# comms_2.net
KiCad netlist of a schematic drawn in EAGLE
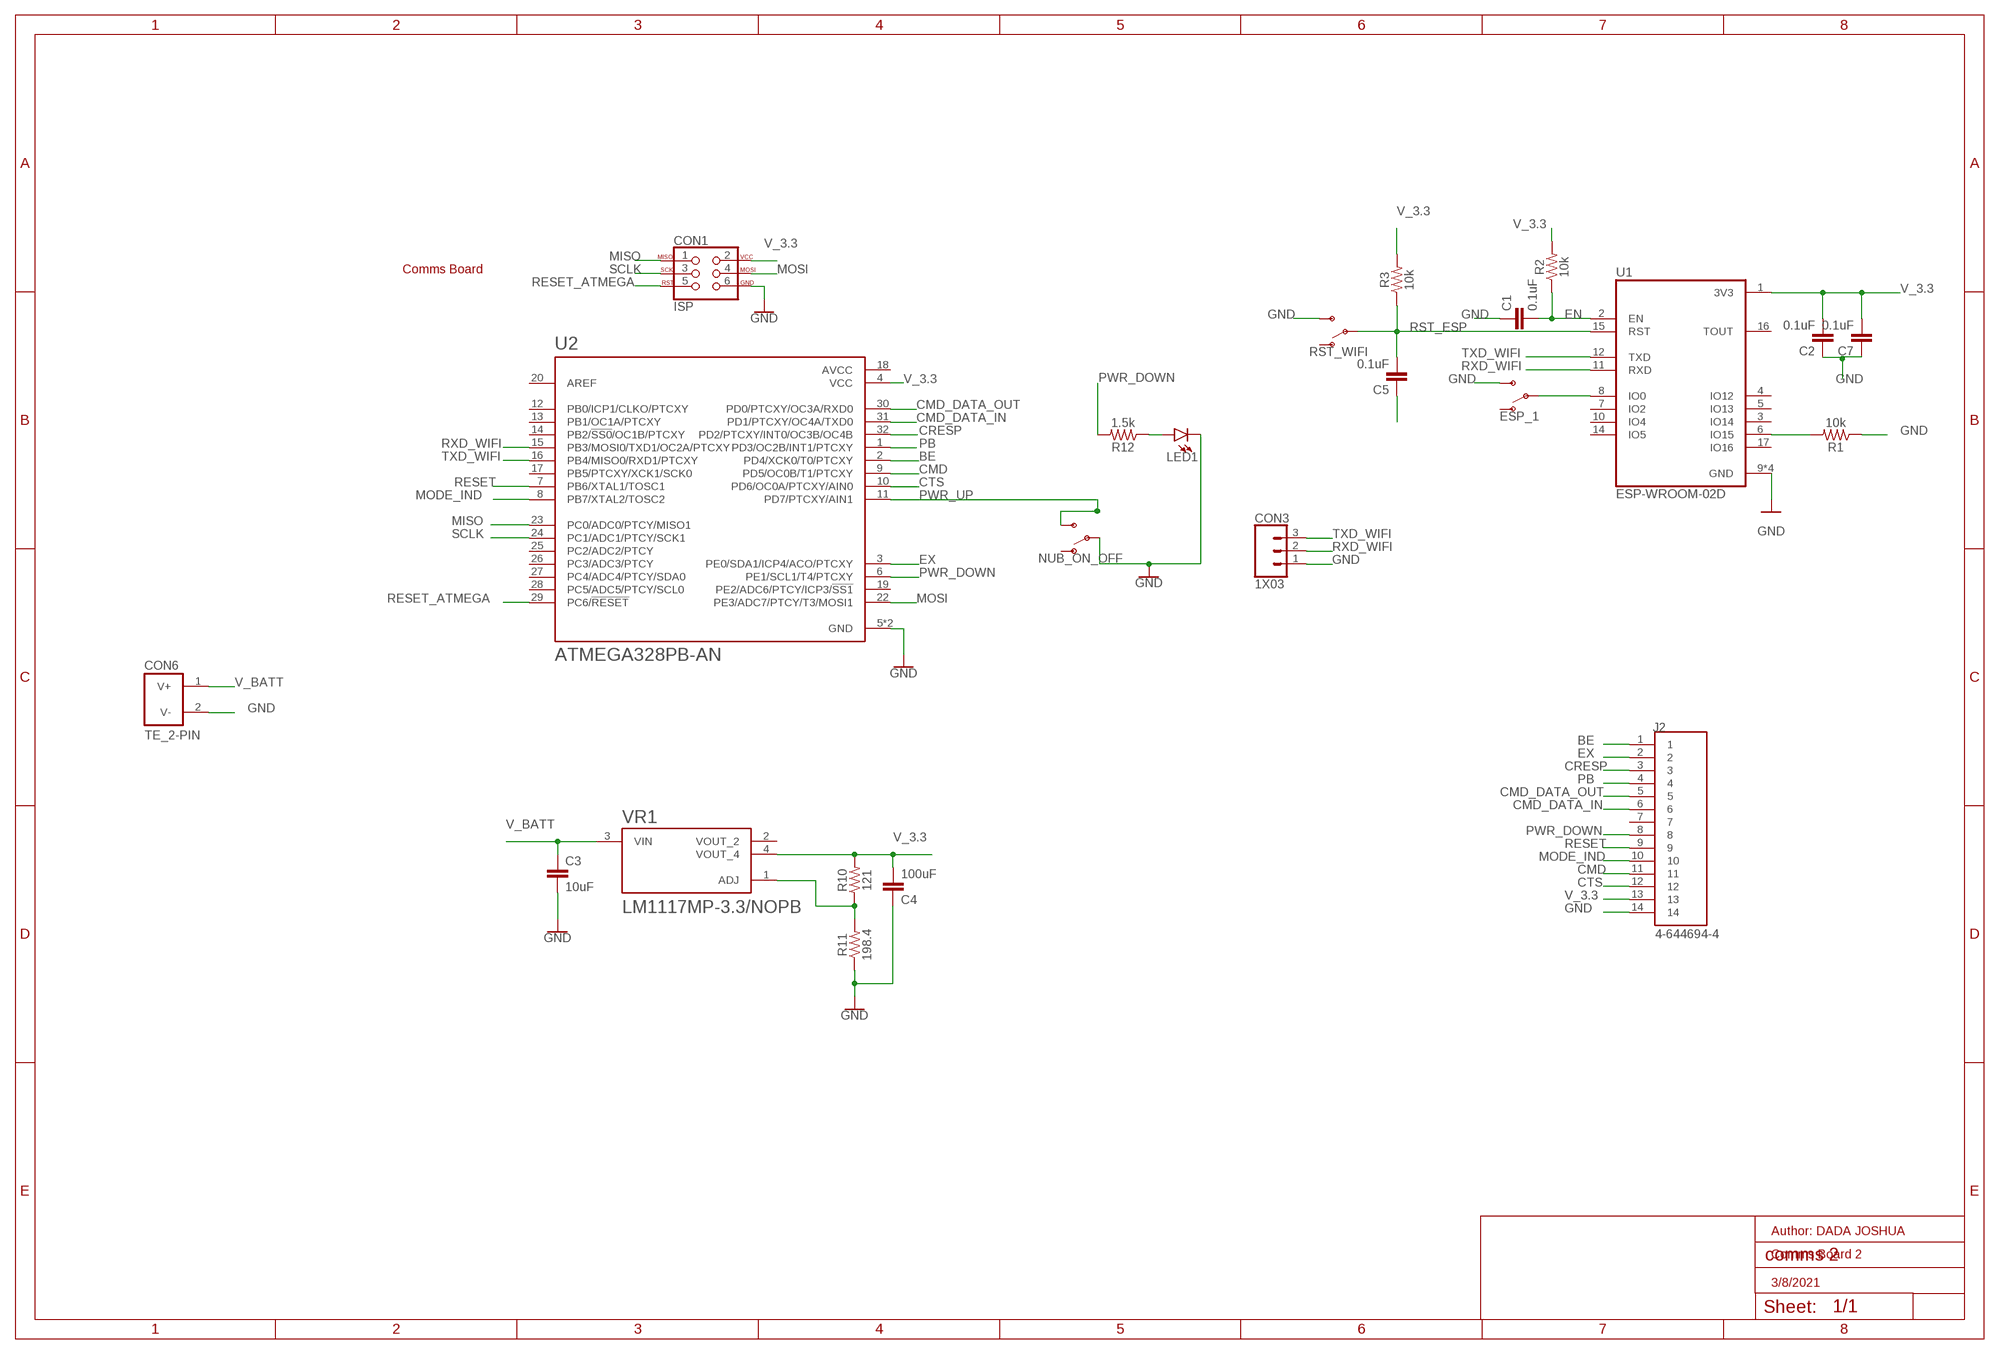
[diagram p0: schematic, sheet 1]

(export (version "E")
  (design (tool "Eeschema 10.0.6"))
  (components
    (comp (ref "C1")
      (value "0.1uF")
      (footprint "eagle-import:1210")
      (libsource (lib "eagle-import") (part "CAPACITOR_1210"))
    )
    (comp (ref "C2")
      (value "0.1uF")
      (footprint "eagle-import:1210")
      (libsource (lib "eagle-import") (part "CAPACITOR_1210"))
    )
    (comp (ref "C3")
      (value "10uF")
      (footprint "eagle-import:1210")
      (libsource (lib "eagle-import") (part "CAPACITOR_1210"))
    )
    (comp (ref "C4")
      (value "100uF")
      (footprint "eagle-import:1210")
      (libsource (lib "eagle-import") (part "CAPACITOR_1210"))
    )
    (comp (ref "C5")
      (value "0.1uF")
      (footprint "eagle-import:1210")
      (libsource (lib "eagle-import") (part "CAPACITOR_1210"))
    )
    (comp (ref "C7")
      (value "0.1uF")
      (footprint "eagle-import:1210")
      (libsource (lib "eagle-import") (part "CAPACITOR_1210"))
    )
    (comp (ref "CON1")
      (value "ISP")
      (footprint "eagle-import:ISP_CONNECTOR")
      (libsource (lib "eagle-import") (part "ISP"))
    )
    (comp (ref "CON3")
      (value "1X03")
      (footprint "eagle-import:1X03")
      (libsource (lib "eagle-import") (part "1X03"))
    )
    (comp (ref "CON6")
      (value "TE_2-PIN")
      (footprint "eagle-import:TE_2-PIN")
      (libsource (lib "eagle-import") (part "TE_2-PIN"))
    )
    (comp (ref "ESP_1")
      (value "SWITCH_SPDT")
      (footprint "eagle-import:SWITCH_SPDT")
      (libsource (lib "eagle-import") (part "SWITCH_SPDT"))
    )
    (comp (ref "J2")
      (value "4-644694-4")
      (footprint "eagle-import:TE_4-644694-4")
      (fields (field (name "DIGI-KEY_PART_NUMBER") "A30868-ND") (field (name "MF") "TE Connectivity"))
      (libsource (lib "eagle-import") (part "4-644694-4"))
    )
    (comp (ref "LED1")
      (value "LED_THROUGH-HOLE")
      (footprint "eagle-import:LED_THROUGH-HOLE")
      (libsource (lib "eagle-import") (part "LED_THROUGH-HOLE"))
    )
    (comp (ref "NUB_ON_OFF")
      (value "SWITCH_SPDT")
      (footprint "eagle-import:SWITCH_SPDT")
      (libsource (lib "eagle-import") (part "SWITCH_SPDT"))
    )
    (comp (ref "R1")
      (value "10k")
      (footprint "eagle-import:1210")
      (libsource (lib "eagle-import") (part "RESISTOR_1210"))
    )
    (comp (ref "R2")
      (value "10k")
      (footprint "eagle-import:1210")
      (libsource (lib "eagle-import") (part "RESISTOR_1210"))
    )
    (comp (ref "R3")
      (value "10k")
      (footprint "eagle-import:1210")
      (libsource (lib "eagle-import") (part "RESISTOR_1210"))
    )
    (comp (ref "R10")
      (value "121")
      (footprint "eagle-import:1210")
      (libsource (lib "eagle-import") (part "RESISTOR_1210"))
    )
    (comp (ref "R11")
      (value "198.4")
      (footprint "eagle-import:1210")
      (libsource (lib "eagle-import") (part "RESISTOR_1210"))
    )
    (comp (ref "R12")
      (value "1.5k")
      (footprint "eagle-import:1210")
      (libsource (lib "eagle-import") (part "RESISTOR_1210"))
    )
    (comp (ref "RST_WIFI")
      (value "SWITCH_SPDT")
      (footprint "eagle-import:SWITCH_SPDT")
      (libsource (lib "eagle-import") (part "SWITCH_SPDT"))
    )
    (comp (ref "U1")
      (value "ESP-WROOM-02D")
      (footprint "eagle-import:MODULE_ESP-WROOM-02D")
      (fields (field (name "MF") "Espressif Systems"))
      (libsource (lib "eagle-import") (part "ESP-WROOM-02D"))
    )
    (comp (ref "U2")
      (value "ATMEGA328PB-AN")
      (footprint "eagle-import:QFP80P900X900X120-32N")
      (fields (field (name "MF") "Microchip"))
      (libsource (lib "eagle-import") (part "ATMEGA328PB-AN"))
    )
    (comp (ref "VR1")
      (value "LM1117MP-3.3/NOPB")
      (footprint "eagle-import:VREG_LM1117MP-3.3_NOPB")
      (fields (field (name "MF") "Texas Instruments"))
      (libsource (lib "eagle-import") (part "LM1117MP-3.3/NOPB"))
    )
  )
  (nets
    (net (code "1") (name "/AVCC") (class "Default")
      (node (ref "U2") (pin "18") (pinfunction "AVCC_18") (pintype "power_in"))
    )
    (net (code "2") (name "/BE") (class "Default")
      (node (ref "J2") (pin "1") (pinfunction "1_1") (pintype "passive"))
      (node (ref "U2") (pin "2") (pinfunction "PD4/XCK0/T0/PTCXY_2") (pintype "bidirectional"))
    )
    (net (code "3") (name "/CMD") (class "Default")
      (node (ref "J2") (pin "11") (pinfunction "11_11") (pintype "passive"))
      (node (ref "U2") (pin "9") (pinfunction "PD5/OC0B/T1/PTCXY_9") (pintype "bidirectional"))
    )
    (net (code "4") (name "/CMD_DATA_IN") (class "Default")
      (node (ref "J2") (pin "6") (pinfunction "6_6") (pintype "passive"))
      (node (ref "U2") (pin "31") (pinfunction "PD1/PTCXY/OC4A/TXD0_31") (pintype "bidirectional"))
    )
    (net (code "5") (name "/CMD_DATA_OUT") (class "Default")
      (node (ref "J2") (pin "5") (pinfunction "5_5") (pintype "passive"))
      (node (ref "U2") (pin "30") (pinfunction "PD0/PTCXY/OC3A/RXD0_30") (pintype "bidirectional"))
    )
    (net (code "6") (name "/CRESP") (class "Default")
      (node (ref "J2") (pin "3") (pinfunction "3_3") (pintype "passive"))
      (node (ref "U2") (pin "32") (pinfunction "PD2/PTCXY/INT0/OC3B/OC4B_32") (pintype "bidirectional"))
    )
    (net (code "7") (name "/CTS") (class "Default")
      (node (ref "J2") (pin "12") (pinfunction "12_12") (pintype "passive"))
      (node (ref "U2") (pin "10") (pinfunction "PD6/OC0A/PTCXY/AIN0_10") (pintype "bidirectional"))
    )
    (net (code "8") (name "/EN") (class "Default")
      (node (ref "C1") (pin "2") (pinfunction "2_2") (pintype "passive"))
      (node (ref "R2") (pin "1") (pinfunction "1_1") (pintype "passive"))
      (node (ref "U1") (pin "2") (pinfunction "EN_2") (pintype "input"))
    )
    (net (code "9") (name "/EX") (class "Default")
      (node (ref "J2") (pin "2") (pinfunction "2_2") (pintype "passive"))
      (node (ref "U2") (pin "3") (pinfunction "PE0/SDA1/ICP4/ACO/PTCXY_3") (pintype "bidirectional"))
    )
    (net (code "10") (name "/MISO") (class "Default")
      (node (ref "CON1") (pin "1") (pinfunction "1_1") (pintype "passive"))
      (node (ref "U2") (pin "23") (pinfunction "PC0/ADC0/PTCY/MISO1_23") (pintype "bidirectional"))
    )
    (net (code "11") (name "/MODE_IND") (class "Default")
      (node (ref "J2") (pin "10") (pinfunction "10_10") (pintype "passive"))
      (node (ref "U2") (pin "8") (pinfunction "PB7/XTAL2/TOSC2_8") (pintype "bidirectional"))
    )
    (net (code "12") (name "/MOSI") (class "Default")
      (node (ref "CON1") (pin "4") (pinfunction "4_4") (pintype "passive"))
      (node (ref "U2") (pin "22") (pinfunction "PE3/ADC7/PTCY/T3/MOSI1_22") (pintype "bidirectional"))
    )
    (net (code "13") (name "/PB") (class "Default")
      (node (ref "J2") (pin "4") (pinfunction "4_4") (pintype "passive"))
      (node (ref "U2") (pin "1") (pinfunction "PD3/OC2B/INT1/PTCXY_1") (pintype "bidirectional"))
    )
    (net (code "14") (name "/PWR_DOWN") (class "Default")
      (node (ref "J2") (pin "8") (pinfunction "8_8") (pintype "passive"))
      (node (ref "R12") (pin "2") (pinfunction "2_2") (pintype "passive"))
      (node (ref "U2") (pin "6") (pinfunction "PE1/SCL1/T4/PTCXY_6") (pintype "bidirectional"))
    )
    (net (code "15") (name "/PWR_UP") (class "Default")
      (node (ref "NUB_ON_OFF") (pin "3") (pinfunction "S_3") (pintype "passive"))
      (node (ref "U2") (pin "11") (pinfunction "PD7/PTCXY/AIN1_11") (pintype "bidirectional"))
    )
    (net (code "16") (name "/RESET") (class "Default")
      (node (ref "J2") (pin "9") (pinfunction "9_9") (pintype "passive"))
      (node (ref "U2") (pin "7") (pinfunction "PB6/XTAL1/TOSC1_7") (pintype "bidirectional"))
    )
    (net (code "17") (name "/RESET_ATMEGA") (class "Default")
      (node (ref "CON1") (pin "5") (pinfunction "5_5") (pintype "passive"))
      (node (ref "U2") (pin "29") (pinfunction "PC6/~{RESET}_29") (pintype "bidirectional"))
    )
    (net (code "18") (name "/RST_ESP") (class "Default")
      (node (ref "C5") (pin "2") (pinfunction "2_2") (pintype "passive"))
      (node (ref "R3") (pin "1") (pinfunction "1_1") (pintype "passive"))
      (node (ref "RST_WIFI") (pin "2") (pinfunction "P_2") (pintype "passive"))
      (node (ref "U1") (pin "15") (pinfunction "RST_15") (pintype "input"))
    )
    (net (code "19") (name "/RXD_WIFI") (class "Default")
      (node (ref "CON3") (pin "2") (pinfunction "2_2") (pintype "passive"))
      (node (ref "U1") (pin "11") (pinfunction "RXD_11") (pintype "bidirectional"))
      (node (ref "U2") (pin "15") (pinfunction "PB3/MOSI0/TXD1/OC2A/PTCXY_15") (pintype "bidirectional"))
    )
    (net (code "20") (name "/SCLK") (class "Default")
      (node (ref "CON1") (pin "3") (pinfunction "3_3") (pintype "passive"))
      (node (ref "U2") (pin "24") (pinfunction "PC1/ADC1/PTCY/SCK1_24") (pintype "bidirectional"))
    )
    (net (code "21") (name "/TXD_WIFI") (class "Default")
      (node (ref "CON3") (pin "3") (pinfunction "3_3") (pintype "passive"))
      (node (ref "U1") (pin "12") (pinfunction "TXD_12") (pintype "bidirectional"))
      (node (ref "U2") (pin "16") (pinfunction "PB4/MISO0/RXD1/PTCXY_16") (pintype "bidirectional"))
    )
    (net (code "22") (name "/V_3.3") (class "Default")
      (node (ref "C2") (pin "2") (pinfunction "2_2") (pintype "passive"))
      (node (ref "C4") (pin "2") (pinfunction "2_2") (pintype "passive"))
      (node (ref "C7") (pin "2") (pinfunction "2_2") (pintype "passive"))
      (node (ref "CON1") (pin "2") (pinfunction "2_2") (pintype "passive"))
      (node (ref "J2") (pin "13") (pinfunction "13_13") (pintype "passive"))
      (node (ref "R10") (pin "2") (pinfunction "2_2") (pintype "passive"))
      (node (ref "R2") (pin "2") (pinfunction "2_2") (pintype "passive"))
      (node (ref "R3") (pin "2") (pinfunction "2_2") (pintype "passive"))
      (node (ref "U1") (pin "1") (pinfunction "3V3_1") (pintype "power_in"))
      (node (ref "U2") (pin "4") (pinfunction "VCC_4") (pintype "power_in"))
      (node (ref "VR1") (pin "4") (pinfunction "VOUT_4_4") (pintype "output"))
    )
    (net (code "23") (name "/V_BATT") (class "Default")
      (node (ref "C3") (pin "1") (pinfunction "1_1") (pintype "passive"))
      (node (ref "CON6") (pin "1") (pinfunction "V+_1") (pintype "passive"))
      (node (ref "VR1") (pin "3") (pinfunction "VIN_3") (pintype "input"))
    )
    (net (code "24") (name "GND") (class "Default")
      (node (ref "C1") (pin "1") (pinfunction "1_1") (pintype "passive"))
      (node (ref "C2") (pin "1") (pinfunction "1_1") (pintype "passive"))
      (node (ref "C3") (pin "2") (pinfunction "2_2") (pintype "passive"))
      (node (ref "C4") (pin "1") (pinfunction "1_1") (pintype "passive"))
      (node (ref "C5") (pin "1") (pinfunction "1_1") (pintype "passive"))
      (node (ref "C7") (pin "1") (pinfunction "1_1") (pintype "passive"))
      (node (ref "CON1") (pin "6") (pinfunction "6_6") (pintype "passive"))
      (node (ref "CON3") (pin "1") (pinfunction "1_1") (pintype "passive"))
      (node (ref "CON6") (pin "2") (pinfunction "V-_2") (pintype "passive"))
      (node (ref "ESP_1") (pin "3") (pinfunction "S_3") (pintype "passive"))
      (node (ref "J2") (pin "14") (pinfunction "14_14") (pintype "passive"))
      (node (ref "LED1") (pin "C") (pinfunction "C_C") (pintype "passive"))
      (node (ref "NUB_ON_OFF") (pin "2") (pinfunction "P_2") (pintype "passive"))
      (node (ref "R1") (pin "1") (pinfunction "1_1") (pintype "passive"))
      (node (ref "R11") (pin "1") (pinfunction "1_1") (pintype "passive"))
      (node (ref "RST_WIFI") (pin "3") (pinfunction "S_3") (pintype "passive"))
      (node (ref "U1") (pin "13") (pinfunction "GND_13") (pintype "power_in"))
      (node (ref "U1") (pin "18") (pinfunction "GND_18") (pintype "power_in"))
      (node (ref "U1") (pin "19") (pinfunction "GND_19") (pintype "power_in"))
      (node (ref "U1") (pin "9") (pinfunction "GND_9") (pintype "power_in"))
      (node (ref "U2") (pin "21") (pinfunction "GND_21") (pintype "power_in"))
      (node (ref "U2") (pin "5") (pinfunction "GND_5") (pintype "power_in"))
    )
    (net (code "25") (name "Net-(ESP_1-P)") (class "Default")
      (node (ref "ESP_1") (pin "2") (pinfunction "P_2") (pintype "passive"))
      (node (ref "U1") (pin "8") (pinfunction "IO0_8") (pintype "bidirectional"))
    )
    (net (code "26") (name "Net-(LED1-PadA)") (class "Default")
      (node (ref "LED1") (pin "A") (pinfunction "A_A") (pintype "passive"))
      (node (ref "R12") (pin "1") (pinfunction "1_1") (pintype "passive"))
    )
    (net (code "27") (name "Net-(U1-IO15)") (class "Default")
      (node (ref "R1") (pin "2") (pinfunction "2_2") (pintype "passive"))
      (node (ref "U1") (pin "6") (pinfunction "IO15_6") (pintype "bidirectional"))
    )
    (net (code "28") (name "Net-(VR1-ADJ)") (class "Default")
      (node (ref "R10") (pin "1") (pinfunction "1_1") (pintype "passive"))
      (node (ref "R11") (pin "2") (pinfunction "2_2") (pintype "passive"))
      (node (ref "VR1") (pin "1") (pinfunction "ADJ_1") (pintype "power_in"))
    )
    (net (code "29") (name "unconnected-(ESP_1-O-Pad1)") (class "Default")
      (node (ref "ESP_1") (pin "1") (pinfunction "O_1") (pintype "passive"))
    )
    (net (code "30") (name "unconnected-(J2-Pad7)") (class "Default")
      (node (ref "J2") (pin "7") (pinfunction "7_7") (pintype "passive"))
    )
    (net (code "31") (name "unconnected-(NUB_ON_OFF-O-Pad1)") (class "Default")
      (node (ref "NUB_ON_OFF") (pin "1") (pinfunction "O_1") (pintype "passive"))
    )
    (net (code "32") (name "unconnected-(RST_WIFI-O-Pad1)") (class "Default")
      (node (ref "RST_WIFI") (pin "1") (pinfunction "O_1") (pintype "passive"))
    )
    (net (code "33") (name "unconnected-(U1-IO2-Pad7)") (class "Default")
      (node (ref "U1") (pin "7") (pinfunction "IO2_7") (pintype "bidirectional"))
    )
    (net (code "34") (name "unconnected-(U1-IO4-Pad10)") (class "Default")
      (node (ref "U1") (pin "10") (pinfunction "IO4_10") (pintype "bidirectional"))
    )
    (net (code "35") (name "unconnected-(U1-IO5-Pad14)") (class "Default")
      (node (ref "U1") (pin "14") (pinfunction "IO5_14") (pintype "bidirectional"))
    )
    (net (code "36") (name "unconnected-(U1-IO12-Pad4)") (class "Default")
      (node (ref "U1") (pin "4") (pinfunction "IO12_4") (pintype "bidirectional"))
    )
    (net (code "37") (name "unconnected-(U1-IO13-Pad5)") (class "Default")
      (node (ref "U1") (pin "5") (pinfunction "IO13_5") (pintype "bidirectional"))
    )
    (net (code "38") (name "unconnected-(U1-IO14-Pad3)") (class "Default")
      (node (ref "U1") (pin "3") (pinfunction "IO14_3") (pintype "bidirectional"))
    )
    (net (code "39") (name "unconnected-(U1-IO16-Pad17)") (class "Default")
      (node (ref "U1") (pin "17") (pinfunction "IO16_17") (pintype "bidirectional"))
    )
    (net (code "40") (name "unconnected-(U1-TOUT-Pad16)") (class "Default")
      (node (ref "U1") (pin "16") (pinfunction "TOUT_16") (pintype "bidirectional"))
    )
    (net (code "41") (name "unconnected-(U2-AREF-Pad20)") (class "Default")
      (node (ref "U2") (pin "20") (pinfunction "AREF_20") (pintype "input"))
    )
    (net (code "42") (name "unconnected-(U2-PB0{slash}ICP1{slash}CLKO{slash}PTCXY-Pad12)") (class "Default")
      (node (ref "U2") (pin "12") (pinfunction "PB0/ICP1/CLKO/PTCXY_12") (pintype "bidirectional"))
    )
    (net (code "43") (name "unconnected-(U2-PB1{slash}OC1A{slash}PTCXY-Pad13)") (class "Default")
      (node (ref "U2") (pin "13") (pinfunction "PB1/OC1A/PTCXY_13") (pintype "bidirectional"))
    )
    (net (code "44") (name "unconnected-(U2-PB2{slash}~{SS0}{slash}OC1B{slash}PTCXY-Pad14)") (class "Default")
      (node (ref "U2") (pin "14") (pinfunction "PB2/~{SS0}/OC1B/PTCXY_14") (pintype "bidirectional"))
    )
    (net (code "45") (name "unconnected-(U2-PB5{slash}PTCXY{slash}XCK1{slash}SCK0-Pad17)") (class "Default")
      (node (ref "U2") (pin "17") (pinfunction "PB5/PTCXY/XCK1/SCK0_17") (pintype "bidirectional"))
    )
    (net (code "46") (name "unconnected-(U2-PC2{slash}ADC2{slash}PTCY-Pad25)") (class "Default")
      (node (ref "U2") (pin "25") (pinfunction "PC2/ADC2/PTCY_25") (pintype "bidirectional"))
    )
    (net (code "47") (name "unconnected-(U2-PC3{slash}ADC3{slash}PTCY-Pad26)") (class "Default")
      (node (ref "U2") (pin "26") (pinfunction "PC3/ADC3/PTCY_26") (pintype "bidirectional"))
    )
    (net (code "48") (name "unconnected-(U2-PC4{slash}ADC4{slash}PTCY{slash}SDA0-Pad27)") (class "Default")
      (node (ref "U2") (pin "27") (pinfunction "PC4/ADC4/PTCY/SDA0_27") (pintype "bidirectional"))
    )
    (net (code "49") (name "unconnected-(U2-PC5{slash}ADC5{slash}PTCY{slash}SCL0-Pad28)") (class "Default")
      (node (ref "U2") (pin "28") (pinfunction "PC5/ADC5/PTCY/SCL0_28") (pintype "bidirectional"))
    )
    (net (code "50") (name "unconnected-(U2-PE2{slash}ADC6{slash}PTCY{slash}ICP3{slash}~{SS1}-Pad19)") (class "Default")
      (node (ref "U2") (pin "19") (pinfunction "PE2/ADC6/PTCY/ICP3/~{SS1}_19") (pintype "bidirectional"))
    )
    (net (code "51") (name "unconnected-(VR1-VOUT_2-Pad2)") (class "Default")
      (node (ref "VR1") (pin "2") (pinfunction "VOUT_2_2") (pintype "output"))
    )
  )
)
